# CAO_DMX.net
KiCad netlist of a schematic drawn in Altium Designer
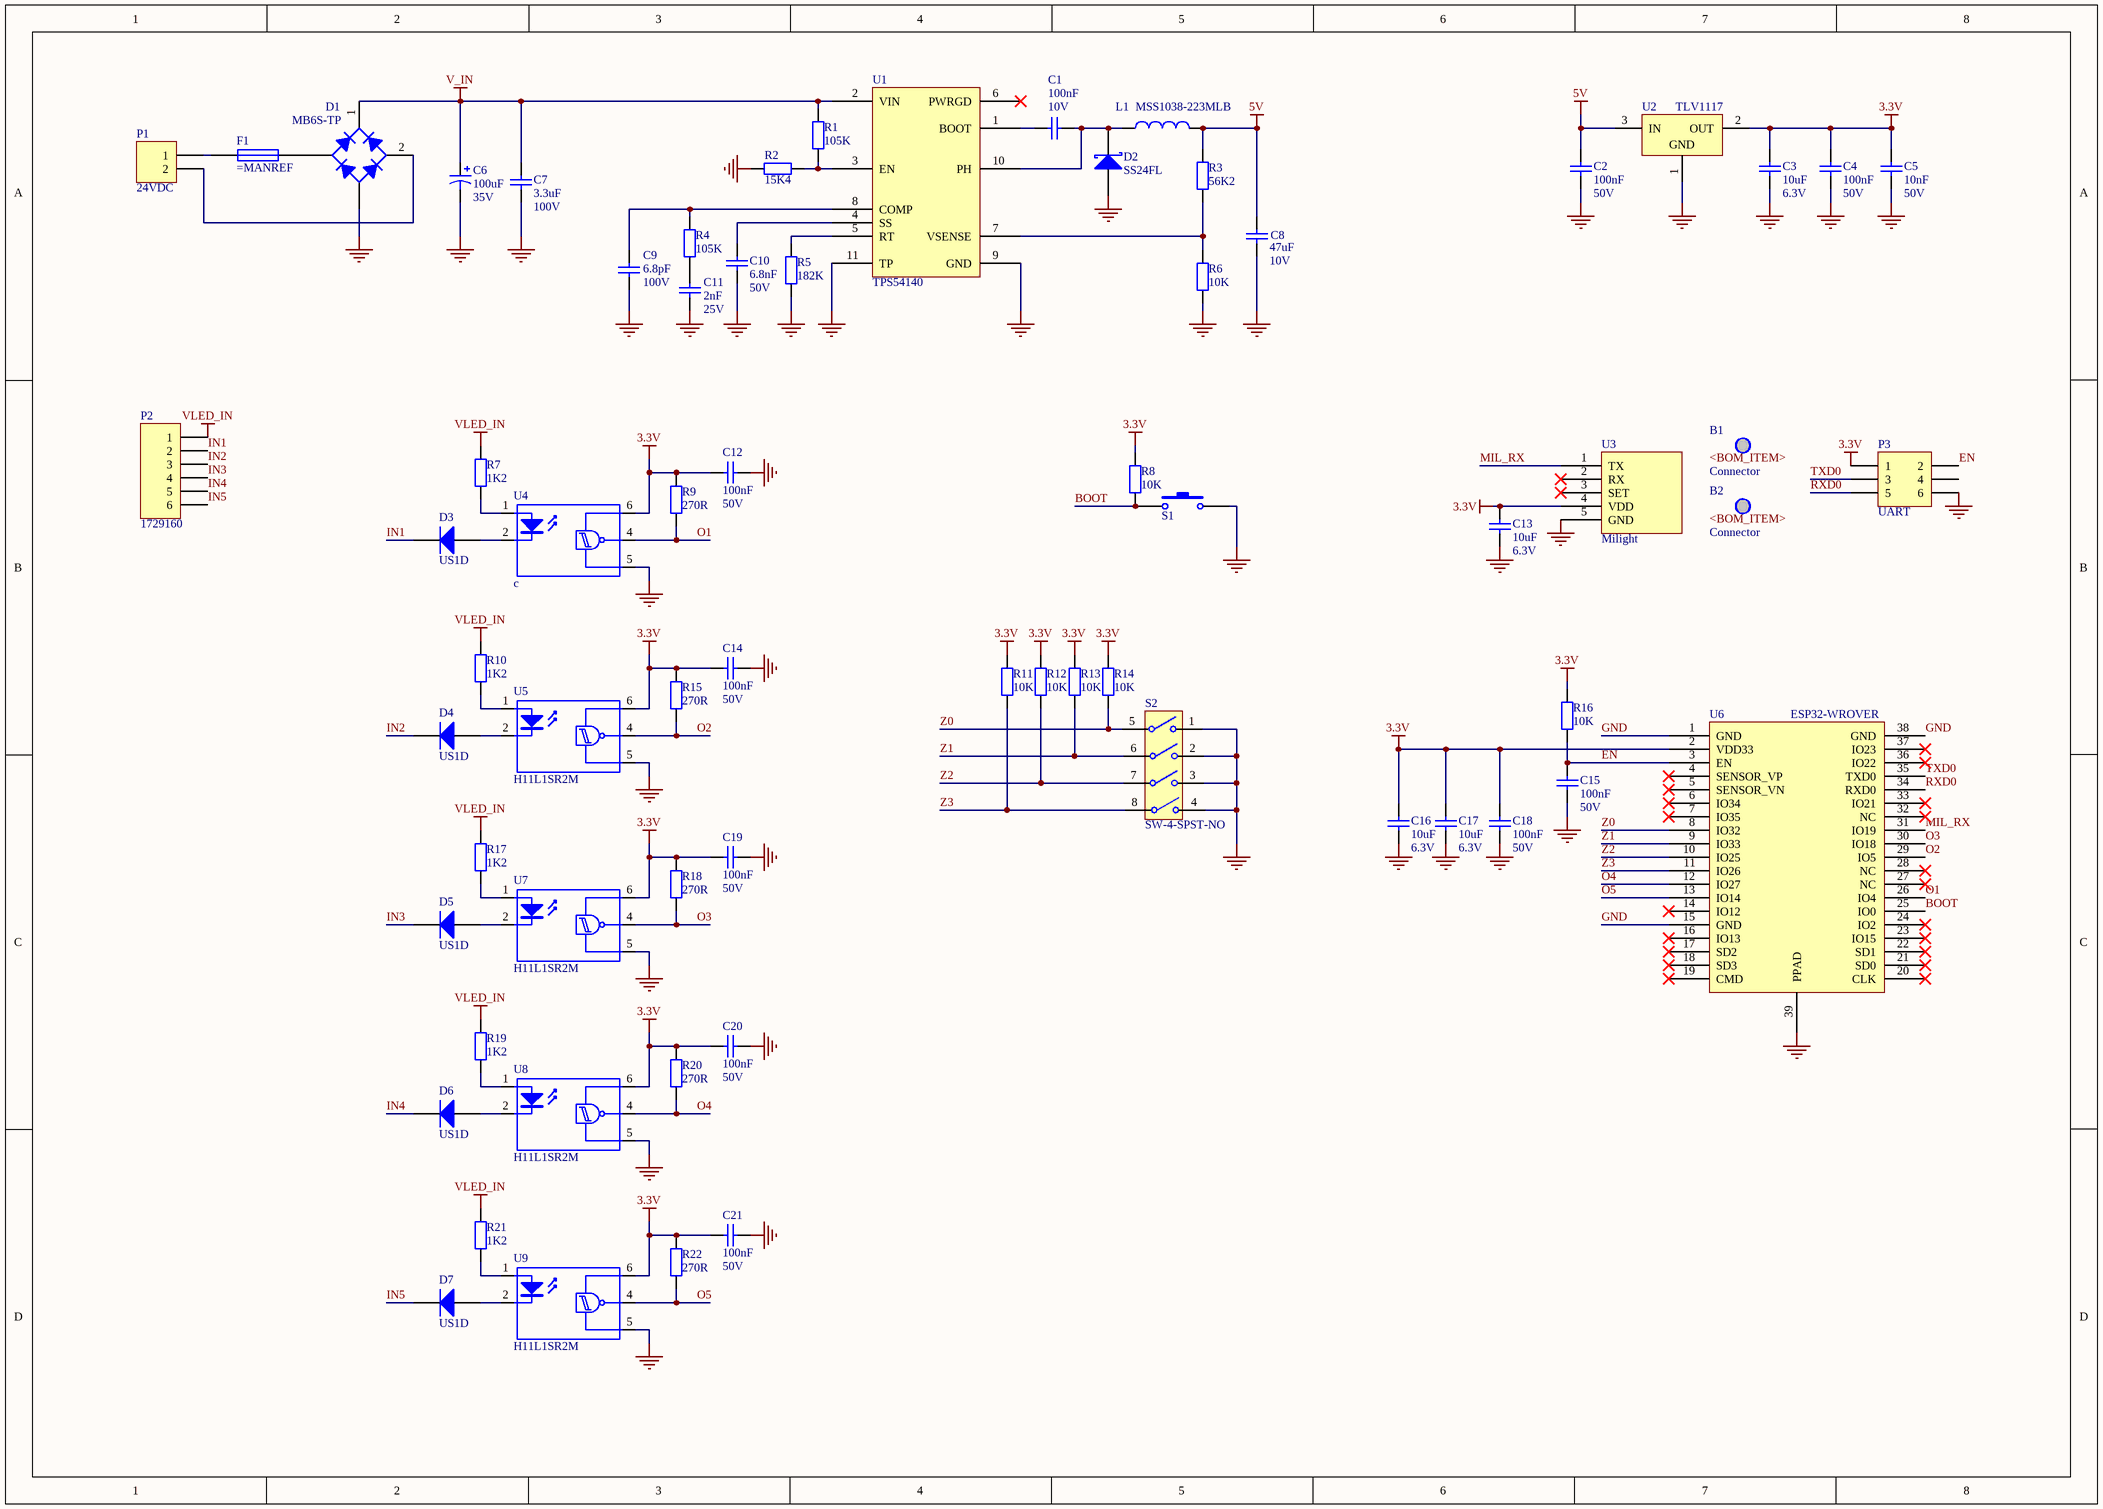
[diagram p0: CAO_DMX.SchDoc]

(export (version "E")
  (design (tool "Eeschema 10.0.6"))
  (components
    (comp (ref "B1")
      (value "Connector")
      (description "BOM item")
      (fields (field (name "PART NUMBER") "MIS-000000019"))
      (libsource (lib "MdtPartDB") (part "Bom_Item"))
    )
    (comp (ref "B2")
      (value "Connector")
      (description "BOM item")
      (fields (field (name "PART NUMBER") "MIS-000000019"))
      (libsource (lib "MdtPartDB") (part "Bom_Item"))
    )
    (comp (ref "C1")
      (value "Capacitor")
      (footprint "CAPC1608N")
      (fields
        (field (name "PART NUMBER") "CAP-000000040")
        (field (name "VALUE 1") "100nF")
        (field (name "VALUE 2") "10V")
      )
      (libsource (lib "MdtPartDB") (part "Capacitor"))
    )
    (comp (ref "C2")
      (value "Capacitor")
      (footprint "CAPC1608N")
      (fields
        (field (name "VALUE 1") "100nF")
        (field (name "VALUE 2") "50V")
        (field (name "PART NUMBER") "CAP-000000003")
      )
      (libsource (lib "MdtPartDB") (part "Capacitor"))
    )
    (comp (ref "C3")
      (value "Capacitor")
      (footprint "CAPC2012N")
      (fields
        (field (name "PART NUMBER") "CAP-000000042")
        (field (name "VALUE 1") "10uF")
        (field (name "VALUE 2") "6.3V")
      )
      (libsource (lib "MdtPartDB") (part "Capacitor"))
    )
    (comp (ref "C4")
      (value "Capacitor")
      (footprint "CAPC1608N")
      (fields
        (field (name "VALUE 1") "100nF")
        (field (name "VALUE 2") "50V")
        (field (name "PART NUMBER") "CAP-000000003")
      )
      (libsource (lib "MdtPartDB") (part "Capacitor"))
    )
    (comp (ref "C5")
      (value "Capacitor")
      (footprint "CAPC1608N")
      (fields
        (field (name "VALUE 1") "10nF")
        (field (name "VALUE 2") "50V")
        (field (name "PART NUMBER") "CAP-000000002")
      )
      (libsource (lib "MdtPartDB") (part "Capacitor"))
    )
    (comp (ref "C6")
      (value "Polarized Capacitor")
      (footprint "ECAP_SMD_6.3")
      (fields
        (field (name "PART NUMBER") "CAP-000000008")
        (field (name "VALUE 1") "100uF")
        (field (name "VALUE 2") "35V")
      )
      (libsource (lib "MdtPartDB") (part "CPolarized"))
    )
    (comp (ref "C7")
      (value "Capacitor")
      (footprint "CAPC3216N")
      (fields
        (field (name "PART NUMBER") "CAP-000000036")
        (field (name "VALUE 1") "3.3uF")
        (field (name "VALUE 2") "100V")
      )
      (libsource (lib "MdtPartDB") (part "Capacitor"))
    )
    (comp (ref "C8")
      (value "Capacitor")
      (footprint "CAPC2012N")
      (fields
        (field (name "PART NUMBER") "CAP-000000041")
        (field (name "VALUE 1") "47uF")
        (field (name "VALUE 2") "10V")
      )
      (libsource (lib "MdtPartDB") (part "Capacitor"))
    )
    (comp (ref "C9")
      (value "Capacitor")
      (footprint "CAPC1608N")
      (fields
        (field (name "PART NUMBER") "CAP-000000037")
        (field (name "VALUE 1") "6.8pF")
        (field (name "VALUE 2") "100V")
      )
      (libsource (lib "MdtPartDB") (part "Capacitor"))
    )
    (comp (ref "C10")
      (value "Capacitor")
      (footprint "CAPC1608N")
      (fields
        (field (name "PART NUMBER") "CAP-000000039")
        (field (name "VALUE 1") "6.8nF")
        (field (name "VALUE 2") "50V")
      )
      (libsource (lib "MdtPartDB") (part "Capacitor"))
    )
    (comp (ref "C11")
      (value "Capacitor")
      (footprint "CAPC2012N")
      (fields
        (field (name "PART NUMBER") "CAP-000000038")
        (field (name "VALUE 1") "2nF")
        (field (name "VALUE 2") "25V")
      )
      (libsource (lib "MdtPartDB") (part "Capacitor"))
    )
    (comp (ref "C12")
      (value "Capacitor")
      (footprint "CAPC1608N")
      (fields
        (field (name "PART NUMBER") "CAP-000000003")
        (field (name "VALUE 1") "100nF")
        (field (name "VALUE 2") "50V")
      )
      (libsource (lib "MdtPartDB") (part "Capacitor"))
    )
    (comp (ref "C13")
      (value "Capacitor")
      (footprint "CAPC2012N")
      (fields
        (field (name "PART NUMBER") "CAP-000000042")
        (field (name "VALUE 1") "10uF")
        (field (name "VALUE 2") "6.3V")
      )
      (libsource (lib "MdtPartDB") (part "Capacitor"))
    )
    (comp (ref "C14")
      (value "Capacitor")
      (footprint "CAPC1608N")
      (fields
        (field (name "PART NUMBER") "CAP-000000003")
        (field (name "VALUE 1") "100nF")
        (field (name "VALUE 2") "50V")
      )
      (libsource (lib "MdtPartDB") (part "Capacitor"))
    )
    (comp (ref "C15")
      (value "Capacitor")
      (footprint "CAPC1608N")
      (fields
        (field (name "PART NUMBER") "CAP-000000003")
        (field (name "VALUE 1") "100nF")
        (field (name "VALUE 2") "50V")
      )
      (libsource (lib "MdtPartDB") (part "Capacitor"))
    )
    (comp (ref "C16")
      (value "Capacitor")
      (footprint "CAPC2012N")
      (fields
        (field (name "PART NUMBER") "CAP-000000042")
        (field (name "VALUE 1") "10uF")
        (field (name "VALUE 2") "6.3V")
      )
      (libsource (lib "MdtPartDB") (part "Capacitor"))
    )
    (comp (ref "C17")
      (value "Capacitor")
      (footprint "CAPC2012N")
      (fields
        (field (name "PART NUMBER") "CAP-000000042")
        (field (name "VALUE 1") "10uF")
        (field (name "VALUE 2") "6.3V")
      )
      (libsource (lib "MdtPartDB") (part "Capacitor"))
    )
    (comp (ref "C18")
      (value "Capacitor")
      (footprint "CAPC1608N")
      (fields
        (field (name "PART NUMBER") "CAP-000000003")
        (field (name "VALUE 1") "100nF")
        (field (name "VALUE 2") "50V")
      )
      (libsource (lib "MdtPartDB") (part "Capacitor"))
    )
    (comp (ref "C19")
      (value "Capacitor")
      (footprint "CAPC1608N")
      (fields
        (field (name "PART NUMBER") "CAP-000000003")
        (field (name "VALUE 1") "100nF")
        (field (name "VALUE 2") "50V")
      )
      (libsource (lib "MdtPartDB") (part "Capacitor"))
    )
    (comp (ref "C20")
      (value "Capacitor")
      (footprint "CAPC1608N")
      (fields
        (field (name "PART NUMBER") "CAP-000000003")
        (field (name "VALUE 1") "100nF")
        (field (name "VALUE 2") "50V")
      )
      (libsource (lib "MdtPartDB") (part "Capacitor"))
    )
    (comp (ref "C21")
      (value "Capacitor")
      (footprint "CAPC1608N")
      (fields
        (field (name "PART NUMBER") "CAP-000000003")
        (field (name "VALUE 1") "100nF")
        (field (name "VALUE 2") "50V")
      )
      (libsource (lib "MdtPartDB") (part "Capacitor"))
    )
    (comp (ref "D1")
      (value "MB6S-TP")
      (footprint "MB6S")
      (description "Full Wave Diode Bridge")
      (fields (field (name "PART NUMBER") "DIB-000000002"))
      (libsource (lib "MdtPartDB") (part "DBridge"))
    )
    (comp (ref "D2")
      (value "SS24FL")
      (footprint "SOD-123F")
      (description "Schottky Diode")
      (fields (field (name "PART NUMBER") "DIS-000000016"))
      (libsource (lib "MdtPartDB") (part "DSchottky"))
    )
    (comp (ref "D3")
      (value "US1D")
      (footprint "DO-214AC")
      (description "Diode")
      (fields (field (name "PART NUMBER") "DIR-000000002"))
      (libsource (lib "MdtPartDB") (part "Diode"))
    )
    (comp (ref "D4")
      (value "US1D")
      (footprint "DO-214AC")
      (description "Diode")
      (fields (field (name "PART NUMBER") "DIR-000000002"))
      (libsource (lib "MdtPartDB") (part "Diode"))
    )
    (comp (ref "D5")
      (value "US1D")
      (footprint "DO-214AC")
      (description "Diode")
      (fields (field (name "PART NUMBER") "DIR-000000002"))
      (libsource (lib "MdtPartDB") (part "Diode"))
    )
    (comp (ref "D6")
      (value "US1D")
      (footprint "DO-214AC")
      (description "Diode")
      (fields (field (name "PART NUMBER") "DIR-000000002"))
      (libsource (lib "MdtPartDB") (part "Diode"))
    )
    (comp (ref "D7")
      (value "US1D")
      (footprint "DO-214AC")
      (description "Diode")
      (fields (field (name "PART NUMBER") "DIR-000000002"))
      (libsource (lib "MdtPartDB") (part "Diode"))
    )
    (comp (ref "F1") (value "~") (description "Fuse") (libsource (lib "GNSS") (part "Fuse")))
    (comp (ref "L1")
      (value "MSS1038-223MLB")
      (footprint "MSS1038")
      (description "Inductor")
      (fields (field (name "PART NUMBER") "IND-000000012"))
      (libsource (lib "MdtPartDB") (part "Inductor"))
    )
    (comp (ref "P1")
      (value "24VDC")
      (footprint "*TE_282843-2")
      (description "Header, 2-Pin")
      (fields (field (name "PART NUMBER") "CON-000000036"))
      (libsource (lib "MdtPartDB") (part "Header 2"))
    )
    (comp (ref "P2")
      (value "1729160")
      (footprint "1729160")
      (description "Header, 6-Pin")
      (fields (field (name "PART NUMBER") "CON-000000035"))
      (libsource (lib "MdtPartDB") (part "Header 6"))
    )
    (comp (ref "P3")
      (value "UART")
      (footprint "HDR2X3")
      (description "Header, 3-Pin, Dual row")
      (fields (field (name "PART NUMBER") "CON-000000012"))
      (libsource (lib "MdtPartDB") (part "Header 2X3"))
    )
    (comp (ref "R1")
      (value "Resistor")
      (footprint "RESC1608N")
      (fields (field (name "PART NUMBER") "RES-000000070") (field (name "VALUE 1") "105K"))
      (libsource (lib "MdtPartDB") (part "Resistor"))
    )
    (comp (ref "R2")
      (value "Resistor")
      (footprint "RESC1608N")
      (fields (field (name "PART NUMBER") "RES-000000085") (field (name "VALUE 1") "15K4"))
      (libsource (lib "") (part "Resistor_1"))
    )
    (comp (ref "R3")
      (value "Resistor")
      (footprint "RESC1608N")
      (fields (field (name "PART NUMBER") "RES-000000086") (field (name "VALUE 1") "56K2"))
      (libsource (lib "MdtPartDB") (part "Resistor"))
    )
    (comp (ref "R4")
      (value "Resistor")
      (footprint "RESC1608N")
      (fields (field (name "PART NUMBER") "RES-000000070") (field (name "VALUE 1") "105K"))
      (libsource (lib "MdtPartDB") (part "Resistor"))
    )
    (comp (ref "R5")
      (value "Resistor")
      (footprint "RESC1608N")
      (fields (field (name "PART NUMBER") "RES-000000084") (field (name "VALUE 1") "182K"))
      (libsource (lib "MdtPartDB") (part "Resistor"))
    )
    (comp (ref "R6")
      (value "Resistor")
      (footprint "RESC1608N")
      (fields (field (name "PART NUMBER") "RES-000000003") (field (name "VALUE 1") "10K"))
      (libsource (lib "MdtPartDB") (part "Resistor"))
    )
    (comp (ref "R7")
      (value "Resistor")
      (footprint "RESC6432N")
      (fields (field (name "PART NUMBER") "RES-000000095") (field (name "VALUE 1") "1K2"))
      (libsource (lib "MdtPartDB") (part "Resistor"))
    )
    (comp (ref "R8")
      (value "Resistor")
      (footprint "RESC1608N")
      (fields (field (name "PART NUMBER") "RES-000000003") (field (name "VALUE 1") "10K"))
      (libsource (lib "MdtPartDB") (part "Resistor"))
    )
    (comp (ref "R9")
      (value "Resistor")
      (footprint "RESC1608N")
      (fields (field (name "PART NUMBER") "RES-000000094") (field (name "VALUE 1") "270R"))
      (libsource (lib "MdtPartDB") (part "Resistor"))
    )
    (comp (ref "R10")
      (value "Resistor")
      (footprint "RESC6432N")
      (fields (field (name "PART NUMBER") "RES-000000095") (field (name "VALUE 1") "1K2"))
      (libsource (lib "MdtPartDB") (part "Resistor"))
    )
    (comp (ref "R11")
      (value "Resistor")
      (footprint "RESC1608N")
      (fields (field (name "PART NUMBER") "RES-000000003") (field (name "VALUE 1") "10K"))
      (libsource (lib "MdtPartDB") (part "Resistor"))
    )
    (comp (ref "R12")
      (value "Resistor")
      (footprint "RESC1608N")
      (fields (field (name "PART NUMBER") "RES-000000003") (field (name "VALUE 1") "10K"))
      (libsource (lib "MdtPartDB") (part "Resistor"))
    )
    (comp (ref "R13")
      (value "Resistor")
      (footprint "RESC1608N")
      (fields (field (name "PART NUMBER") "RES-000000003") (field (name "VALUE 1") "10K"))
      (libsource (lib "MdtPartDB") (part "Resistor"))
    )
    (comp (ref "R14")
      (value "Resistor")
      (footprint "RESC1608N")
      (fields (field (name "PART NUMBER") "RES-000000003") (field (name "VALUE 1") "10K"))
      (libsource (lib "MdtPartDB") (part "Resistor"))
    )
    (comp (ref "R15")
      (value "Resistor")
      (footprint "RESC1608N")
      (fields (field (name "PART NUMBER") "RES-000000094") (field (name "VALUE 1") "270R"))
      (libsource (lib "MdtPartDB") (part "Resistor"))
    )
    (comp (ref "R16")
      (value "Resistor")
      (footprint "RESC1608N")
      (fields (field (name "PART NUMBER") "RES-000000003") (field (name "VALUE 1") "10K"))
      (libsource (lib "MdtPartDB") (part "Resistor"))
    )
    (comp (ref "R17")
      (value "Resistor")
      (footprint "RESC6432N")
      (fields (field (name "PART NUMBER") "RES-000000095") (field (name "VALUE 1") "1K2"))
      (libsource (lib "MdtPartDB") (part "Resistor"))
    )
    (comp (ref "R18")
      (value "Resistor")
      (footprint "RESC1608N")
      (fields (field (name "PART NUMBER") "RES-000000094") (field (name "VALUE 1") "270R"))
      (libsource (lib "MdtPartDB") (part "Resistor"))
    )
    (comp (ref "R19")
      (value "Resistor")
      (footprint "RESC6432N")
      (fields (field (name "PART NUMBER") "RES-000000095") (field (name "VALUE 1") "1K2"))
      (libsource (lib "MdtPartDB") (part "Resistor"))
    )
    (comp (ref "R20")
      (value "Resistor")
      (footprint "RESC1608N")
      (fields (field (name "PART NUMBER") "RES-000000094") (field (name "VALUE 1") "270R"))
      (libsource (lib "MdtPartDB") (part "Resistor"))
    )
    (comp (ref "R21")
      (value "Resistor")
      (footprint "RESC6432N")
      (fields (field (name "PART NUMBER") "RES-000000095") (field (name "VALUE 1") "1K2"))
      (libsource (lib "MdtPartDB") (part "Resistor"))
    )
    (comp (ref "R22")
      (value "Resistor")
      (footprint "RESC1608N")
      (fields (field (name "PART NUMBER") "RES-000000094") (field (name "VALUE 1") "270R"))
      (libsource (lib "MdtPartDB") (part "Resistor"))
    )
    (comp (ref "S1")
      (value "Switch")
      (footprint "FSM4")
      (fields (field (name "PART NUMBER") "MIS-000000020"))
      (libsource (lib "MdtPartDB") (part "SW-PB"))
    )
    (comp (ref "S2")
      (value "SW-4-SPST-NO")
      (footprint "418117270904")
      (fields (field (name "PART NUMBER") "SWC-000000004"))
      (libsource (lib "MdtPartDB") (part "SW-4-SPST-NO"))
    )
    (comp (ref "U1")
      (value "TPS54140")
      (footprint "VSON-10")
      (description "4-V to 40-V, 1-A Step-Down Converter With High Efficiency Eco-Mode")
      (fields (field (name "PART NUMBER") "ICP-000000006"))
      (libsource (lib "MdtPartDB") (part "TPS54140A"))
    )
    (comp (ref "U2")
      (value "TLV1117")
      (footprint "SOT223")
      (description "Voltage Regulator")
      (fields (field (name "PART NUMBER") "VRG-000000001"))
      (libsource (lib "MdtPartDB") (part "TLV1117"))
    )
    (comp (ref "U3")
      (value "Milight")
      (footprint "MILIGHT_RF_MODULE")
      (fields (field (name "PART NUMBER") "RFC-000000003"))
      (libsource (lib "MdtPartDB") (part "Milight_RF"))
    )
    (comp (ref "U4")
      (value "c")
      (footprint "DIP-6")
      (description "Schmitt Trigger Output Optocoupler")
      (fields (field (name "PART NUMBER") "OPT-000000005"))
      (libsource (lib "MdtPartDB") (part "Optoisolator_Digital"))
    )
    (comp (ref "U5")
      (value "H11L1SR2M")
      (footprint "DIP-6")
      (description "Schmitt Trigger Output Optocoupler")
      (fields (field (name "PART NUMBER") "OPT-000000005"))
      (libsource (lib "MdtPartDB") (part "Optoisolator_Digital"))
    )
    (comp (ref "U6")
      (value "ESP32-WROVER")
      (footprint "ESP32-WROVER")
      (description "Modules WiFi / 802.11 SMD Module, ESP32-D0WDQ6, 32Mbits PSRAM, 32Mbits SPI flash, PCB Antenna")
      (fields (field (name "PART NUMBER") "RFC-000000002"))
      (libsource (lib "MdtPartDB") (part "ESP32-WROVER"))
    )
    (comp (ref "U7")
      (value "H11L1SR2M")
      (footprint "DIP-6")
      (description "Schmitt Trigger Output Optocoupler")
      (fields (field (name "PART NUMBER") "OPT-000000005"))
      (libsource (lib "MdtPartDB") (part "Optoisolator_Digital"))
    )
    (comp (ref "U8")
      (value "H11L1SR2M")
      (footprint "DIP-6")
      (description "Schmitt Trigger Output Optocoupler")
      (fields (field (name "PART NUMBER") "OPT-000000005"))
      (libsource (lib "MdtPartDB") (part "Optoisolator_Digital"))
    )
    (comp (ref "U9")
      (value "H11L1SR2M")
      (footprint "DIP-6")
      (description "Schmitt Trigger Output Optocoupler")
      (fields (field (name "PART NUMBER") "OPT-000000005"))
      (libsource (lib "MdtPartDB") (part "Optoisolator_Digital"))
    )
  )
  (nets
    (net (code "1") (name "/BOOT") (class "Default")
      (node (ref "R8") (pin "1") (pinfunction "1_1") (pintype "passive"))
      (node (ref "S1") (pin "1") (pinfunction "1_1") (pintype "passive"))
      (node (ref "U6") (pin "25") (pinfunction "IO0_25") (pintype "passive"))
    )
    (net (code "2") (name "/EN") (class "Default")
      (node (ref "C15") (pin "2") (pinfunction "2_2") (pintype "passive"))
      (node (ref "P3") (pin "2") (pinfunction "2_2") (pintype "passive"))
      (node (ref "R16") (pin "1") (pinfunction "1_1") (pintype "passive"))
      (node (ref "U6") (pin "3") (pinfunction "EN_3") (pintype "passive"))
    )
    (net (code "3") (name "/IN1") (class "Default")
      (node (ref "D3") (pin "2") (pinfunction "K_2") (pintype "passive"))
      (node (ref "P2") (pin "2") (pinfunction "2_2") (pintype "passive"))
    )
    (net (code "4") (name "/IN2") (class "Default")
      (node (ref "D4") (pin "2") (pinfunction "K_2") (pintype "passive"))
      (node (ref "P2") (pin "3") (pinfunction "3_3") (pintype "passive"))
    )
    (net (code "5") (name "/IN3") (class "Default")
      (node (ref "D5") (pin "2") (pinfunction "K_2") (pintype "passive"))
      (node (ref "P2") (pin "4") (pinfunction "4_4") (pintype "passive"))
    )
    (net (code "6") (name "/IN4") (class "Default")
      (node (ref "D6") (pin "2") (pinfunction "K_2") (pintype "passive"))
      (node (ref "P2") (pin "5") (pinfunction "5_5") (pintype "passive"))
    )
    (net (code "7") (name "/IN5") (class "Default")
      (node (ref "D7") (pin "2") (pinfunction "K_2") (pintype "passive"))
      (node (ref "P2") (pin "6") (pinfunction "6_6") (pintype "passive"))
    )
    (net (code "8") (name "/MIL_RX") (class "Default")
      (node (ref "U3") (pin "1") (pinfunction "TX_1") (pintype "passive"))
      (node (ref "U6") (pin "31") (pinfunction "IO19_31") (pintype "passive"))
    )
    (net (code "9") (name "/O1") (class "Default")
      (node (ref "R9") (pin "1") (pinfunction "1_1") (pintype "passive"))
      (node (ref "U4") (pin "4") (pinfunction "VO_4") (pintype "passive"))
      (node (ref "U6") (pin "26") (pinfunction "IO4_26") (pintype "passive"))
    )
    (net (code "10") (name "/O2") (class "Default")
      (node (ref "R15") (pin "1") (pinfunction "1_1") (pintype "passive"))
      (node (ref "U5") (pin "4") (pinfunction "VO_4") (pintype "passive"))
      (node (ref "U6") (pin "29") (pinfunction "IO5_29") (pintype "passive"))
    )
    (net (code "11") (name "/O3") (class "Default")
      (node (ref "R18") (pin "1") (pinfunction "1_1") (pintype "passive"))
      (node (ref "U6") (pin "30") (pinfunction "IO18_30") (pintype "passive"))
      (node (ref "U7") (pin "4") (pinfunction "VO_4") (pintype "passive"))
    )
    (net (code "12") (name "/O4") (class "Default")
      (node (ref "R20") (pin "1") (pinfunction "1_1") (pintype "passive"))
      (node (ref "U6") (pin "12") (pinfunction "IO27_12") (pintype "passive"))
      (node (ref "U8") (pin "4") (pinfunction "VO_4") (pintype "passive"))
    )
    (net (code "13") (name "/O5") (class "Default")
      (node (ref "R22") (pin "1") (pinfunction "1_1") (pintype "passive"))
      (node (ref "U6") (pin "13") (pinfunction "IO14_13") (pintype "passive"))
      (node (ref "U9") (pin "4") (pinfunction "VO_4") (pintype "passive"))
    )
    (net (code "14") (name "/RXD0") (class "Default")
      (node (ref "P3") (pin "5") (pinfunction "5_5") (pintype "passive"))
      (node (ref "U6") (pin "34") (pinfunction "RXD0_34") (pintype "passive"))
    )
    (net (code "15") (name "/TXD0") (class "Default")
      (node (ref "P3") (pin "3") (pinfunction "3_3") (pintype "passive"))
      (node (ref "U6") (pin "35") (pinfunction "TXD0_35") (pintype "passive"))
    )
    (net (code "16") (name "/Z0") (class "Default")
      (node (ref "R14") (pin "1") (pinfunction "1_1") (pintype "passive"))
      (node (ref "S2") (pin "5") (pinfunction "5_5") (pintype "passive"))
      (node (ref "U6") (pin "8") (pinfunction "IO32_8") (pintype "passive"))
    )
    (net (code "17") (name "/Z1") (class "Default")
      (node (ref "R13") (pin "1") (pinfunction "1_1") (pintype "passive"))
      (node (ref "S2") (pin "6") (pinfunction "6_6") (pintype "passive"))
      (node (ref "U6") (pin "9") (pinfunction "IO33_9") (pintype "passive"))
    )
    (net (code "18") (name "/Z2") (class "Default")
      (node (ref "R12") (pin "1") (pinfunction "1_1") (pintype "passive"))
      (node (ref "S2") (pin "7") (pinfunction "7_7") (pintype "passive"))
      (node (ref "U6") (pin "10") (pinfunction "IO25_10") (pintype "passive"))
    )
    (net (code "19") (name "/Z3") (class "Default")
      (node (ref "R11") (pin "1") (pinfunction "1_1") (pintype "passive"))
      (node (ref "S2") (pin "8") (pinfunction "8_8") (pintype "passive"))
      (node (ref "U6") (pin "11") (pinfunction "IO26_11") (pintype "passive"))
    )
    (net (code "20") (name "3.3V") (class "Default")
      (node (ref "C12") (pin "2") (pinfunction "2_2") (pintype "passive"))
      (node (ref "C13") (pin "2") (pinfunction "2_2") (pintype "passive"))
      (node (ref "C14") (pin "2") (pinfunction "2_2") (pintype "passive"))
      (node (ref "C16") (pin "2") (pinfunction "2_2") (pintype "passive"))
      (node (ref "C17") (pin "2") (pinfunction "2_2") (pintype "passive"))
      (node (ref "C18") (pin "2") (pinfunction "2_2") (pintype "passive"))
      (node (ref "C19") (pin "2") (pinfunction "2_2") (pintype "passive"))
      (node (ref "C20") (pin "2") (pinfunction "2_2") (pintype "passive"))
      (node (ref "C21") (pin "2") (pinfunction "2_2") (pintype "passive"))
      (node (ref "C3") (pin "2") (pinfunction "2_2") (pintype "passive"))
      (node (ref "C4") (pin "2") (pinfunction "2_2") (pintype "passive"))
      (node (ref "C5") (pin "2") (pinfunction "2_2") (pintype "passive"))
      (node (ref "P3") (pin "1") (pinfunction "1_1") (pintype "passive"))
      (node (ref "R11") (pin "2") (pinfunction "2_2") (pintype "passive"))
      (node (ref "R12") (pin "2") (pinfunction "2_2") (pintype "passive"))
      (node (ref "R13") (pin "2") (pinfunction "2_2") (pintype "passive"))
      (node (ref "R14") (pin "2") (pinfunction "2_2") (pintype "passive"))
      (node (ref "R15") (pin "2") (pinfunction "2_2") (pintype "passive"))
      (node (ref "R16") (pin "2") (pinfunction "2_2") (pintype "passive"))
      (node (ref "R18") (pin "2") (pinfunction "2_2") (pintype "passive"))
      (node (ref "R20") (pin "2") (pinfunction "2_2") (pintype "passive"))
      (node (ref "R22") (pin "2") (pinfunction "2_2") (pintype "passive"))
      (node (ref "R8") (pin "2") (pinfunction "2_2") (pintype "passive"))
      (node (ref "R9") (pin "2") (pinfunction "2_2") (pintype "passive"))
      (node (ref "U2") (pin "2") (pinfunction "OUT_2") (pintype "power_in"))
      (node (ref "U3") (pin "4") (pinfunction "VDD_4") (pintype "passive"))
      (node (ref "U4") (pin "6") (pinfunction "VCC_6") (pintype "passive"))
      (node (ref "U5") (pin "6") (pinfunction "VCC_6") (pintype "passive"))
      (node (ref "U6") (pin "2") (pinfunction "VDD33_2") (pintype "passive"))
      (node (ref "U7") (pin "6") (pinfunction "VCC_6") (pintype "passive"))
      (node (ref "U8") (pin "6") (pinfunction "VCC_6") (pintype "passive"))
      (node (ref "U9") (pin "6") (pinfunction "VCC_6") (pintype "passive"))
    )
    (net (code "21") (name "5V") (class "Default")
      (node (ref "C2") (pin "2") (pinfunction "2_2") (pintype "passive"))
      (node (ref "C8") (pin "2") (pinfunction "2_2") (pintype "passive"))
      (node (ref "L1") (pin "2") (pinfunction "2_2") (pintype "passive"))
      (node (ref "R3") (pin "2") (pinfunction "2_2") (pintype "passive"))
      (node (ref "U2") (pin "3") (pinfunction "IN_3") (pintype "power_in"))
    )
    (net (code "22") (name "GND") (class "Default")
      (node (ref "C10") (pin "1") (pinfunction "1_1") (pintype "passive"))
      (node (ref "C11") (pin "1") (pinfunction "1_1") (pintype "passive"))
      (node (ref "C12") (pin "1") (pinfunction "1_1") (pintype "passive"))
      (node (ref "C13") (pin "1") (pinfunction "1_1") (pintype "passive"))
      (node (ref "C14") (pin "1") (pinfunction "1_1") (pintype "passive"))
      (node (ref "C15") (pin "1") (pinfunction "1_1") (pintype "passive"))
      (node (ref "C16") (pin "1") (pinfunction "1_1") (pintype "passive"))
      (node (ref "C17") (pin "1") (pinfunction "1_1") (pintype "passive"))
      (node (ref "C18") (pin "1") (pinfunction "1_1") (pintype "passive"))
      (node (ref "C19") (pin "1") (pinfunction "1_1") (pintype "passive"))
      (node (ref "C2") (pin "1") (pinfunction "1_1") (pintype "passive"))
      (node (ref "C20") (pin "1") (pinfunction "1_1") (pintype "passive"))
      (node (ref "C21") (pin "1") (pinfunction "1_1") (pintype "passive"))
      (node (ref "C3") (pin "1") (pinfunction "1_1") (pintype "passive"))
      (node (ref "C4") (pin "1") (pinfunction "1_1") (pintype "passive"))
      (node (ref "C5") (pin "1") (pinfunction "1_1") (pintype "passive"))
      (node (ref "C6") (pin "2") (pinfunction "2_2") (pintype "passive"))
      (node (ref "C7") (pin "1") (pinfunction "1_1") (pintype "passive"))
      (node (ref "C8") (pin "1") (pinfunction "1_1") (pintype "passive"))
      (node (ref "C9") (pin "1") (pinfunction "1_1") (pintype "passive"))
      (node (ref "D1") (pin "3") (pinfunction "A_3") (pintype "passive"))
      (node (ref "D2") (pin "1") (pinfunction "A_1") (pintype "passive"))
      (node (ref "P3") (pin "6") (pinfunction "6_6") (pintype "passive"))
      (node (ref "R2") (pin "1") (pinfunction "1_1") (pintype "passive"))
      (node (ref "R5") (pin "1") (pinfunction "1_1") (pintype "passive"))
      (node (ref "R6") (pin "1") (pinfunction "1_1") (pintype "passive"))
      (node (ref "S1") (pin "2") (pinfunction "2_2") (pintype "passive"))
      (node (ref "S2") (pin "1") (pinfunction "1_1") (pintype "passive"))
      (node (ref "S2") (pin "2") (pinfunction "2_2") (pintype "passive"))
      (node (ref "S2") (pin "3") (pinfunction "3_3") (pintype "passive"))
      (node (ref "S2") (pin "4") (pinfunction "4_4") (pintype "passive"))
      (node (ref "U1") (pin "11") (pinfunction "TP_11") (pintype "passive"))
      (node (ref "U1") (pin "9") (pinfunction "GND_9") (pintype "passive"))
      (node (ref "U2") (pin "1") (pinfunction "GND_1") (pintype "power_in"))
      (node (ref "U3") (pin "5") (pinfunction "GND_5") (pintype "passive"))
      (node (ref "U4") (pin "5") (pinfunction "GND_5") (pintype "passive"))
      (node (ref "U5") (pin "5") (pinfunction "GND_5") (pintype "passive"))
      (node (ref "U6") (pin "1") (pinfunction "GND_1") (pintype "passive"))
      (node (ref "U6") (pin "15") (pinfunction "GND_15") (pintype "passive"))
      (node (ref "U6") (pin "38") (pinfunction "GND_38") (pintype "passive"))
      (node (ref "U6") (pin "39") (pinfunction "PPAD_39") (pintype "passive"))
      (node (ref "U7") (pin "5") (pinfunction "GND_5") (pintype "passive"))
      (node (ref "U8") (pin "5") (pinfunction "GND_5") (pintype "passive"))
      (node (ref "U9") (pin "5") (pinfunction "GND_5") (pintype "passive"))
    )
    (net (code "23") (name "Net-(C11-Pad2)") (class "Default")
      (node (ref "C11") (pin "2") (pinfunction "2_2") (pintype "passive"))
      (node (ref "R4") (pin "1") (pinfunction "1_1") (pintype "passive"))
    )
    (net (code "24") (name "Net-(D1-C-Pad2)") (class "Default")
      (node (ref "D1") (pin "2") (pinfunction "C_2") (pintype "passive"))
      (node (ref "P1") (pin "2") (pinfunction "2_2") (pintype "passive"))
    )
    (net (code "25") (name "Net-(D1-C-Pad4)") (class "Default")
      (node (ref "D1") (pin "4") (pinfunction "C_4") (pintype "passive"))
      (node (ref "F1") (pin "2") (pinfunction "2_2") (pintype "passive"))
    )
    (net (code "26") (name "Net-(D2-K)") (class "Default")
      (node (ref "C1") (pin "2") (pinfunction "2_2") (pintype "passive"))
      (node (ref "D2") (pin "2") (pinfunction "K_2") (pintype "passive"))
      (node (ref "L1") (pin "1") (pinfunction "1_1") (pintype "passive"))
      (node (ref "U1") (pin "10") (pinfunction "PH_10") (pintype "passive"))
    )
    (net (code "27") (name "Net-(D3-A)") (class "Default")
      (node (ref "D3") (pin "1") (pinfunction "A_1") (pintype "passive"))
      (node (ref "U4") (pin "2") (pinfunction "K_2") (pintype "passive"))
    )
    (net (code "28") (name "Net-(D4-A)") (class "Default")
      (node (ref "D4") (pin "1") (pinfunction "A_1") (pintype "passive"))
      (node (ref "U5") (pin "2") (pinfunction "K_2") (pintype "passive"))
    )
    (net (code "29") (name "Net-(D5-A)") (class "Default")
      (node (ref "D5") (pin "1") (pinfunction "A_1") (pintype "passive"))
      (node (ref "U7") (pin "2") (pinfunction "K_2") (pintype "passive"))
    )
    (net (code "30") (name "Net-(D6-A)") (class "Default")
      (node (ref "D6") (pin "1") (pinfunction "A_1") (pintype "passive"))
      (node (ref "U8") (pin "2") (pinfunction "K_2") (pintype "passive"))
    )
    (net (code "31") (name "Net-(D7-A)") (class "Default")
      (node (ref "D7") (pin "1") (pinfunction "A_1") (pintype "passive"))
      (node (ref "U9") (pin "2") (pinfunction "K_2") (pintype "passive"))
    )
    (net (code "32") (name "Net-(F1-Pad1)") (class "Default")
      (node (ref "F1") (pin "1") (pinfunction "1_1") (pintype "passive"))
      (node (ref "P1") (pin "1") (pinfunction "1_1") (pintype "passive"))
    )
    (net (code "33") (name "Net-(U1-BOOT)") (class "Default")
      (node (ref "C1") (pin "1") (pinfunction "1_1") (pintype "passive"))
      (node (ref "U1") (pin "1") (pinfunction "BOOT_1") (pintype "passive"))
    )
    (net (code "34") (name "Net-(U1-COMP)") (class "Default")
      (node (ref "C9") (pin "2") (pinfunction "2_2") (pintype "passive"))
      (node (ref "R4") (pin "2") (pinfunction "2_2") (pintype "passive"))
      (node (ref "U1") (pin "8") (pinfunction "COMP_8") (pintype "passive"))
    )
    (net (code "35") (name "Net-(U1-EN)") (class "Default")
      (node (ref "R1") (pin "1") (pinfunction "1_1") (pintype "passive"))
      (node (ref "R2") (pin "2") (pinfunction "2_2") (pintype "passive"))
      (node (ref "U1") (pin "3") (pinfunction "EN_3") (pintype "passive"))
    )
    (net (code "36") (name "Net-(U1-RT)") (class "Default")
      (node (ref "R5") (pin "2") (pinfunction "2_2") (pintype "passive"))
      (node (ref "U1") (pin "5") (pinfunction "RT_5") (pintype "passive"))
    )
    (net (code "37") (name "Net-(U1-SS)") (class "Default")
      (node (ref "C10") (pin "2") (pinfunction "2_2") (pintype "passive"))
      (node (ref "U1") (pin "4") (pinfunction "SS_4") (pintype "passive"))
    )
    (net (code "38") (name "Net-(U1-VSENSE)") (class "Default")
      (node (ref "R3") (pin "1") (pinfunction "1_1") (pintype "passive"))
      (node (ref "R6") (pin "2") (pinfunction "2_2") (pintype "passive"))
      (node (ref "U1") (pin "7") (pinfunction "VSENSE_7") (pintype "passive"))
    )
    (net (code "39") (name "Net-(U4-A)") (class "Default")
      (node (ref "R7") (pin "1") (pinfunction "1_1") (pintype "passive"))
      (node (ref "U4") (pin "1") (pinfunction "A_1") (pintype "passive"))
    )
    (net (code "40") (name "Net-(U5-A)") (class "Default")
      (node (ref "R10") (pin "1") (pinfunction "1_1") (pintype "passive"))
      (node (ref "U5") (pin "1") (pinfunction "A_1") (pintype "passive"))
    )
    (net (code "41") (name "Net-(U7-A)") (class "Default")
      (node (ref "R17") (pin "1") (pinfunction "1_1") (pintype "passive"))
      (node (ref "U7") (pin "1") (pinfunction "A_1") (pintype "passive"))
    )
    (net (code "42") (name "Net-(U8-A)") (class "Default")
      (node (ref "R19") (pin "1") (pinfunction "1_1") (pintype "passive"))
      (node (ref "U8") (pin "1") (pinfunction "A_1") (pintype "passive"))
    )
    (net (code "43") (name "Net-(U9-A)") (class "Default")
      (node (ref "R21") (pin "1") (pinfunction "1_1") (pintype "passive"))
      (node (ref "U9") (pin "1") (pinfunction "A_1") (pintype "passive"))
    )
    (net (code "44") (name "VLED_IN") (class "Default")
      (node (ref "P2") (pin "1") (pinfunction "1_1") (pintype "passive"))
      (node (ref "R10") (pin "2") (pinfunction "2_2") (pintype "passive"))
      (node (ref "R17") (pin "2") (pinfunction "2_2") (pintype "passive"))
      (node (ref "R19") (pin "2") (pinfunction "2_2") (pintype "passive"))
      (node (ref "R21") (pin "2") (pinfunction "2_2") (pintype "passive"))
      (node (ref "R7") (pin "2") (pinfunction "2_2") (pintype "passive"))
    )
    (net (code "45") (name "V_IN") (class "Default")
      (node (ref "C6") (pin "1") (pinfunction "1_1") (pintype "passive"))
      (node (ref "C7") (pin "2") (pinfunction "2_2") (pintype "passive"))
      (node (ref "D1") (pin "1") (pinfunction "K_1") (pintype "passive"))
      (node (ref "R1") (pin "2") (pinfunction "2_2") (pintype "passive"))
      (node (ref "U1") (pin "2") (pinfunction "VIN_2") (pintype "passive"))
    )
    (net (code "46") (name "unconnected-(P3-Pad4)") (class "Default")
      (node (ref "P3") (pin "4") (pinfunction "4_4") (pintype "passive"))
    )
    (net (code "47") (name "unconnected-(U1-PWRGD-Pad6)") (class "Default")
      (node (ref "U1") (pin "6") (pinfunction "PWRGD_6") (pintype "passive+no_connect"))
    )
    (net (code "48") (name "unconnected-(U3-RX-Pad2)") (class "Default")
      (node (ref "U3") (pin "2") (pinfunction "RX_2") (pintype "passive+no_connect"))
    )
    (net (code "49") (name "unconnected-(U3-SET-Pad3)") (class "Default")
      (node (ref "U3") (pin "3") (pinfunction "SET_3") (pintype "passive+no_connect"))
    )
    (net (code "50") (name "unconnected-(U6-CLK-Pad20)") (class "Default")
      (node (ref "U6") (pin "20") (pinfunction "CLK_20") (pintype "passive+no_connect"))
    )
    (net (code "51") (name "unconnected-(U6-CMD-Pad19)") (class "Default")
      (node (ref "U6") (pin "19") (pinfunction "CMD_19") (pintype "passive+no_connect"))
    )
    (net (code "52") (name "unconnected-(U6-IO2-Pad24)") (class "Default")
      (node (ref "U6") (pin "24") (pinfunction "IO2_24") (pintype "passive+no_connect"))
    )
    (net (code "53") (name "unconnected-(U6-IO12-Pad14)") (class "Default")
      (node (ref "U6") (pin "14") (pinfunction "IO12_14") (pintype "passive+no_connect"))
    )
    (net (code "54") (name "unconnected-(U6-IO13-Pad16)") (class "Default")
      (node (ref "U6") (pin "16") (pinfunction "IO13_16") (pintype "passive+no_connect"))
    )
    (net (code "55") (name "unconnected-(U6-IO15-Pad23)") (class "Default")
      (node (ref "U6") (pin "23") (pinfunction "IO15_23") (pintype "passive+no_connect"))
    )
    (net (code "56") (name "unconnected-(U6-IO21-Pad33)") (class "Default")
      (node (ref "U6") (pin "33") (pinfunction "IO21_33") (pintype "passive+no_connect"))
    )
    (net (code "57") (name "unconnected-(U6-IO22-Pad36)") (class "Default")
      (node (ref "U6") (pin "36") (pinfunction "IO22_36") (pintype "passive+no_connect"))
    )
    (net (code "58") (name "unconnected-(U6-IO23-Pad37)") (class "Default")
      (node (ref "U6") (pin "37") (pinfunction "IO23_37") (pintype "passive+no_connect"))
    )
    (net (code "59") (name "unconnected-(U6-IO34-Pad6)") (class "Default")
      (node (ref "U6") (pin "6") (pinfunction "IO34_6") (pintype "passive+no_connect"))
    )
    (net (code "60") (name "unconnected-(U6-IO35-Pad7)") (class "Default")
      (node (ref "U6") (pin "7") (pinfunction "IO35_7") (pintype "passive+no_connect"))
    )
    (net (code "61") (name "unconnected-(U6-NC-Pad27)") (class "Default")
      (node (ref "U6") (pin "27") (pinfunction "NC_27") (pintype "passive+no_connect"))
    )
    (net (code "62") (name "unconnected-(U6-NC-Pad28)") (class "Default")
      (node (ref "U6") (pin "28") (pinfunction "NC_28") (pintype "passive+no_connect"))
    )
    (net (code "63") (name "unconnected-(U6-NC-Pad32)") (class "Default")
      (node (ref "U6") (pin "32") (pinfunction "NC_32") (pintype "passive+no_connect"))
    )
    (net (code "64") (name "unconnected-(U6-SD0-Pad21)") (class "Default")
      (node (ref "U6") (pin "21") (pinfunction "SD0_21") (pintype "passive+no_connect"))
    )
    (net (code "65") (name "unconnected-(U6-SD1-Pad22)") (class "Default")
      (node (ref "U6") (pin "22") (pinfunction "SD1_22") (pintype "passive+no_connect"))
    )
    (net (code "66") (name "unconnected-(U6-SD2-Pad17)") (class "Default")
      (node (ref "U6") (pin "17") (pinfunction "SD2_17") (pintype "passive+no_connect"))
    )
    (net (code "67") (name "unconnected-(U6-SD3-Pad18)") (class "Default")
      (node (ref "U6") (pin "18") (pinfunction "SD3_18") (pintype "passive+no_connect"))
    )
    (net (code "68") (name "unconnected-(U6-SENSOR_VN-Pad5)") (class "Default")
      (node (ref "U6") (pin "5") (pinfunction "SENSOR_VN_5") (pintype "passive+no_connect"))
    )
    (net (code "69") (name "unconnected-(U6-SENSOR_VP-Pad4)") (class "Default")
      (node (ref "U6") (pin "4") (pinfunction "SENSOR_VP_4") (pintype "passive+no_connect"))
    )
  )
)
